# Mechanical_Holes.net
KiCad netlist of a schematic drawn in Altium Designer
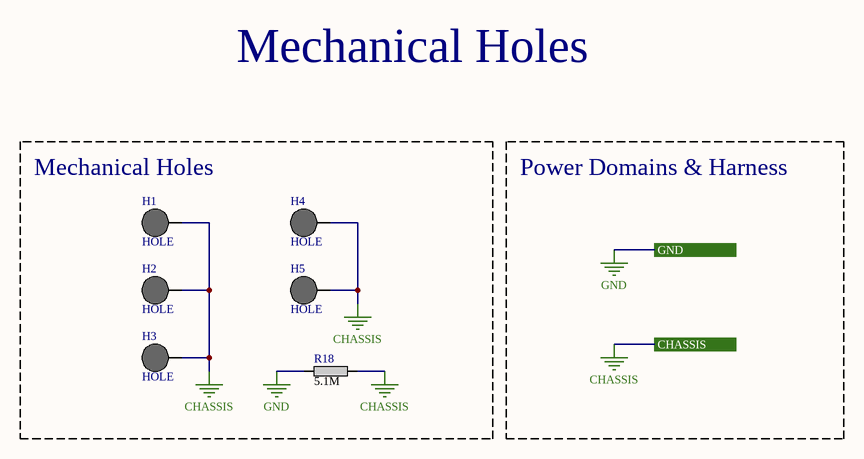
[diagram p0: Mechanical_Holes.SchDoc]

(export (version "E")
  (design (tool "Eeschema 10.0.6"))
  (components
    (comp (ref "H1")
      (value "HOLE")
      (footprint "HOLE_M3")
      (description "Hole M3")
      (libsource (lib "Library") (part "HOLE"))
    )
    (comp (ref "H2")
      (value "HOLE")
      (footprint "HOLE_M3")
      (description "Hole M3")
      (libsource (lib "Library") (part "HOLE"))
    )
    (comp (ref "H3")
      (value "HOLE")
      (footprint "HOLE_M3")
      (description "Hole M3")
      (libsource (lib "Library") (part "HOLE"))
    )
    (comp (ref "H4")
      (value "HOLE")
      (footprint "HOLE_M3")
      (description "Hole M3")
      (libsource (lib "Library") (part "HOLE"))
    )
    (comp (ref "H5")
      (value "HOLE")
      (footprint "HOLE_M3")
      (description "Hole M3")
      (libsource (lib "Library") (part "HOLE"))
    )
    (comp (ref "R18")
      (value "5.1M")
      (footprint "0805")
      (description "125mW Thick Film Resistors ±1% 5.1MΩ 0805  Chip Resistor - Surface Mount ROHS")
      (fields
        (field (name "MANUFACTURER") "TA-I Tech")
        (field (name "MANUFACTURER PART NUMBER") "RM10FTN5104")
      )
      (libsource (lib "Library") (part "RES"))
    )
  )
  (nets
    (net (code "1") (name "CHASSIS") (class "Default")
      (node (ref "H1") (pin "1") (pinfunction "1_1") (pintype "passive"))
      (node (ref "H2") (pin "1") (pinfunction "1_1") (pintype "passive"))
      (node (ref "H3") (pin "1") (pinfunction "1_1") (pintype "passive"))
      (node (ref "H4") (pin "1") (pinfunction "1_1") (pintype "passive"))
      (node (ref "H5") (pin "1") (pinfunction "1_1") (pintype "passive"))
      (node (ref "R18") (pin "1") (pinfunction "1_1") (pintype "passive"))
    )
    (net (code "2") (name "GND") (class "Default")
      (node (ref "R18") (pin "2") (pinfunction "2_2") (pintype "passive"))
    )
  )
)
